# ETH.net
KiCad netlist of a schematic drawn in Altium Designer
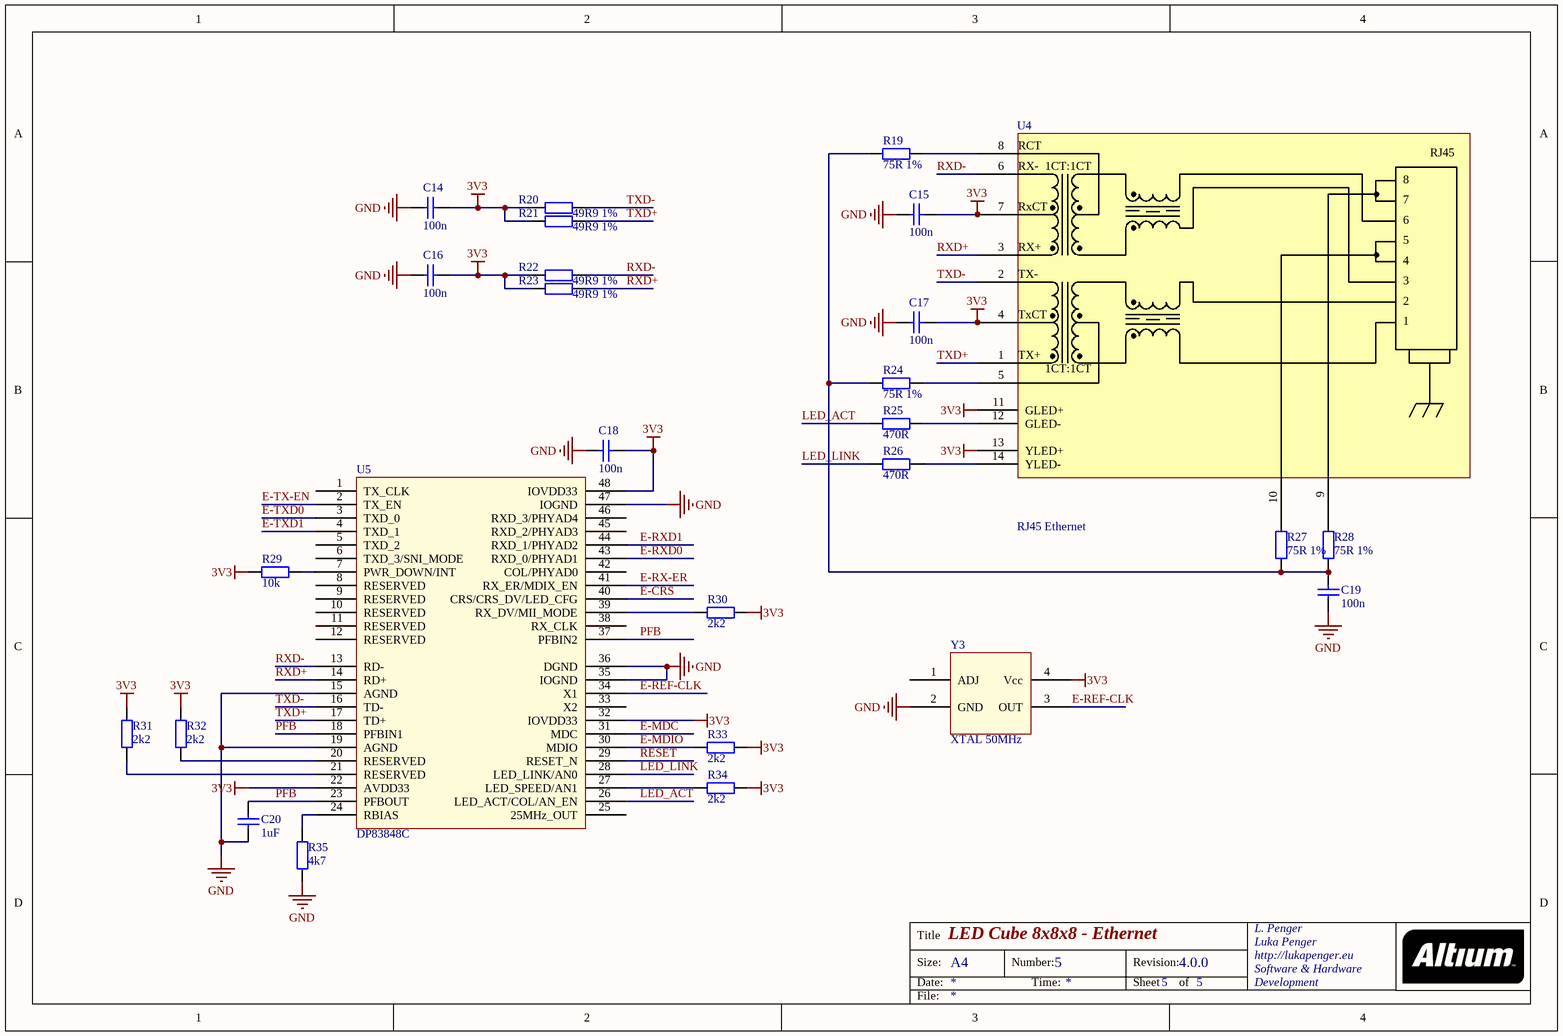
[diagram p0: ETH.SchDoc]

(export (version "E")
  (design (tool "Eeschema 10.0.6"))
  (components
    (comp (ref "C14")
      (value "100n")
      (footprint "1608[0603]")
      (description "Capacitor")
      (fields (field (name "PUBLISHER") "Altium Limited"))
      (libsource (lib "Miscellaneous Devices") (part "Cap"))
    )
    (comp (ref "C15")
      (value "100n")
      (footprint "1608[0603]")
      (description "Capacitor")
      (fields (field (name "PUBLISHER") "Altium Limited"))
      (libsource (lib "Miscellaneous Devices") (part "Cap"))
    )
    (comp (ref "C16")
      (value "100n")
      (footprint "1608[0603]")
      (description "Capacitor")
      (fields (field (name "PUBLISHER") "Altium Limited"))
      (libsource (lib "Miscellaneous Devices") (part "Cap"))
    )
    (comp (ref "C17")
      (value "100n")
      (footprint "1608[0603]")
      (description "Capacitor")
      (fields (field (name "PUBLISHER") "Altium Limited"))
      (libsource (lib "Miscellaneous Devices") (part "Cap"))
    )
    (comp (ref "C18")
      (value "100n")
      (footprint "1608[0603]")
      (description "Capacitor")
      (fields (field (name "PUBLISHER") "Altium Limited"))
      (libsource (lib "Miscellaneous Devices") (part "Cap"))
    )
    (comp (ref "C19")
      (value "100n")
      (footprint "1608[0603]")
      (description "Capacitor")
      (fields (field (name "PUBLISHER") "Altium Limited"))
      (libsource (lib "Miscellaneous Devices") (part "Cap"))
    )
    (comp (ref "C20")
      (value "1uF")
      (footprint "6-0805_L")
      (description "Capacitor")
      (fields (field (name "PUBLISHER") "Altium Limited"))
      (libsource (lib "Miscellaneous Devices") (part "Cap"))
    )
    (comp (ref "R19")
      (value "75R 1%")
      (footprint "1608[0603]")
      (description "Resistor")
      (fields (field (name "PUBLISHER") "Altium Limited"))
      (libsource (lib "Miscellaneous Devices") (part "Res2"))
    )
    (comp (ref "R20")
      (value "49R9 1%")
      (footprint "1608[0603]")
      (description "Resistor")
      (fields (field (name "PUBLISHER") "Altium Limited"))
      (libsource (lib "Miscellaneous Devices") (part "Res2"))
    )
    (comp (ref "R21")
      (value "49R9 1%")
      (footprint "1608[0603]")
      (description "Resistor")
      (fields (field (name "PUBLISHER") "Altium Limited"))
      (libsource (lib "Miscellaneous Devices") (part "Res2"))
    )
    (comp (ref "R22")
      (value "49R9 1%")
      (footprint "1608[0603]")
      (description "Resistor")
      (fields (field (name "PUBLISHER") "Altium Limited"))
      (libsource (lib "Miscellaneous Devices") (part "Res2"))
    )
    (comp (ref "R23")
      (value "49R9 1%")
      (footprint "1608[0603]")
      (description "Resistor")
      (fields (field (name "PUBLISHER") "Altium Limited"))
      (libsource (lib "Miscellaneous Devices") (part "Res2"))
    )
    (comp (ref "R24")
      (value "75R 1%")
      (footprint "1608[0603]")
      (description "Resistor")
      (fields (field (name "PUBLISHER") "Altium Limited"))
      (libsource (lib "Miscellaneous Devices") (part "Res2"))
    )
    (comp (ref "R25")
      (value "470R")
      (footprint "1608[0603]")
      (description "Resistor")
      (fields (field (name "PUBLISHER") "Altium Limited"))
      (libsource (lib "Miscellaneous Devices") (part "Res2"))
    )
    (comp (ref "R26")
      (value "470R")
      (footprint "1608[0603]")
      (description "Resistor")
      (fields (field (name "PUBLISHER") "Altium Limited"))
      (libsource (lib "Miscellaneous Devices") (part "Res2"))
    )
    (comp (ref "R27")
      (value "75R 1%")
      (footprint "1608[0603]")
      (description "Resistor")
      (fields (field (name "PUBLISHER") "Altium Limited"))
      (libsource (lib "") (part "Res2_2"))
    )
    (comp (ref "R28")
      (value "75R 1%")
      (footprint "1608[0603]")
      (description "Resistor")
      (fields (field (name "PUBLISHER") "Altium Limited"))
      (libsource (lib "") (part "Res2_2"))
    )
    (comp (ref "R29")
      (value "10k")
      (footprint "1608[0603]")
      (description "Resistor")
      (fields (field (name "PUBLISHER") "Altium Limited"))
      (libsource (lib "Miscellaneous Devices") (part "Res2"))
    )
    (comp (ref "R30")
      (value "2k2")
      (footprint "1608[0603]")
      (description "Resistor")
      (fields (field (name "PUBLISHER") "Altium Limited"))
      (libsource (lib "Miscellaneous Devices") (part "Res2"))
    )
    (comp (ref "R31")
      (value "2k2")
      (footprint "1608[0603]")
      (description "Resistor")
      (fields (field (name "PUBLISHER") "Altium Limited"))
      (libsource (lib "") (part "Res2_1"))
    )
    (comp (ref "R32")
      (value "2k2")
      (footprint "1608[0603]")
      (description "Resistor")
      (fields (field (name "PUBLISHER") "Altium Limited"))
      (libsource (lib "") (part "Res2_2"))
    )
    (comp (ref "R33")
      (value "2k2")
      (footprint "1608[0603]")
      (description "Resistor")
      (fields (field (name "PUBLISHER") "Altium Limited"))
      (libsource (lib "Miscellaneous Devices") (part "Res2"))
    )
    (comp (ref "R34")
      (value "2k2")
      (footprint "1608[0603]")
      (description "Resistor")
      (fields (field (name "PUBLISHER") "Altium Limited"))
      (libsource (lib "Miscellaneous Devices") (part "Res2"))
    )
    (comp (ref "R35")
      (value "4k7")
      (footprint "1608[0603]")
      (description "Resistor")
      (fields (field (name "PUBLISHER") "Altium Limited"))
      (libsource (lib "") (part "Res2_1"))
    )
    (comp (ref "U4")
      (value "RJ45 Ethernet")
      (footprint "RJ45 Ethernet connector")
      (description "Ethernet Connector")
      (libsource (lib "LP_Lib") (part "RJ45 Ethernet"))
    )
    (comp (ref "U5")
      (value "DP83848C")
      (footprint "DP83848C")
      (description "Ethernet PHY")
      (libsource (lib "LP_Lib") (part "DP83848C"))
    )
    (comp (ref "Y3")
      (value "XTAL 50MHz")
      (footprint "XTAL ACT9200")
      (libsource (lib "LP_Lib") (part "XTAL ACT9200"))
    )
  )
  (nets
    (net (code "1") (name "/E-CRS") (class "Default")
      (node (ref "U5") (pin "40") (pinfunction "CRS/CRS_DV/LED_CFG_40") (pintype "passive"))
    )
    (net (code "2") (name "/E-MDC") (class "Default")
      (node (ref "U5") (pin "31") (pinfunction "MDC_31") (pintype "passive"))
    )
    (net (code "3") (name "/E-MDIO") (class "Default")
      (node (ref "R33") (pin "2") (pinfunction "2_2") (pintype "passive"))
      (node (ref "U5") (pin "30") (pinfunction "MDIO_30") (pintype "passive"))
    )
    (net (code "4") (name "/E-REF-CLK") (class "Default")
      (node (ref "U5") (pin "34") (pinfunction "X1_34") (pintype "passive"))
      (node (ref "Y3") (pin "3") (pinfunction "OUT_3") (pintype "passive"))
    )
    (net (code "5") (name "/E-RX-ER") (class "Default")
      (node (ref "U5") (pin "41") (pinfunction "RX_ER/MDIX_EN_41") (pintype "passive"))
    )
    (net (code "6") (name "/E-RXD0") (class "Default")
      (node (ref "U5") (pin "43") (pinfunction "RXD_0/PHYAD1_43") (pintype "passive"))
    )
    (net (code "7") (name "/E-RXD1") (class "Default")
      (node (ref "U5") (pin "44") (pinfunction "RXD_1/PHYAD2_44") (pintype "passive"))
    )
    (net (code "8") (name "/E-TX-EN") (class "Default")
      (node (ref "U5") (pin "2") (pinfunction "TX_EN_2") (pintype "passive"))
    )
    (net (code "9") (name "/E-TXD0") (class "Default")
      (node (ref "U5") (pin "3") (pinfunction "TXD_0_3") (pintype "passive"))
    )
    (net (code "10") (name "/E-TXD1") (class "Default")
      (node (ref "U5") (pin "4") (pinfunction "TXD_1_4") (pintype "passive"))
    )
    (net (code "11") (name "/LED_ACT") (class "Default")
      (node (ref "R25") (pin "2") (pinfunction "2_2") (pintype "passive"))
      (node (ref "U5") (pin "26") (pinfunction "LED_ACT/COL/AN_EN_26") (pintype "passive"))
    )
    (net (code "12") (name "/LED_LINK") (class "Default")
      (node (ref "R26") (pin "2") (pinfunction "2_2") (pintype "passive"))
      (node (ref "U5") (pin "28") (pinfunction "LED_LINK/AN0_28") (pintype "passive"))
    )
    (net (code "13") (name "/PFB") (class "Default")
      (node (ref "C20") (pin "1") (pinfunction "1_1") (pintype "passive"))
      (node (ref "U5") (pin "18") (pinfunction "PFBIN1_18") (pintype "passive"))
      (node (ref "U5") (pin "23") (pinfunction "PFBOUT_23") (pintype "passive"))
      (node (ref "U5") (pin "37") (pinfunction "PFBIN2_37") (pintype "passive"))
    )
    (net (code "14") (name "/RESET") (class "Default")
      (node (ref "U5") (pin "29") (pinfunction "RESET_N_29") (pintype "passive"))
    )
    (net (code "15") (name "/RXD+") (class "Default")
      (node (ref "R23") (pin "1") (pinfunction "1_1") (pintype "passive"))
      (node (ref "U4") (pin "3") (pintype "passive"))
      (node (ref "U5") (pin "14") (pinfunction "RD+_14") (pintype "passive"))
    )
    (net (code "16") (name "/RXD-") (class "Default")
      (node (ref "R22") (pin "1") (pinfunction "1_1") (pintype "passive"))
      (node (ref "U4") (pin "6") (pintype "passive"))
      (node (ref "U5") (pin "13") (pinfunction "RD-_13") (pintype "passive"))
    )
    (net (code "17") (name "/TXD+") (class "Default")
      (node (ref "R21") (pin "1") (pinfunction "1_1") (pintype "passive"))
      (node (ref "U4") (pin "1") (pintype "passive"))
      (node (ref "U5") (pin "17") (pinfunction "TD+_17") (pintype "passive"))
    )
    (net (code "18") (name "/TXD-") (class "Default")
      (node (ref "R20") (pin "1") (pinfunction "1_1") (pintype "passive"))
      (node (ref "U4") (pin "2") (pintype "passive"))
      (node (ref "U5") (pin "16") (pinfunction "TD-_16") (pintype "passive"))
    )
    (net (code "19") (name "3V3") (class "Default")
      (node (ref "C14") (pin "2") (pinfunction "2_2") (pintype "passive"))
      (node (ref "C15") (pin "2") (pinfunction "2_2") (pintype "passive"))
      (node (ref "C16") (pin "2") (pinfunction "2_2") (pintype "passive"))
      (node (ref "C17") (pin "2") (pinfunction "2_2") (pintype "passive"))
      (node (ref "C18") (pin "2") (pinfunction "2_2") (pintype "passive"))
      (node (ref "R20") (pin "2") (pinfunction "2_2") (pintype "passive"))
      (node (ref "R21") (pin "2") (pinfunction "2_2") (pintype "passive"))
      (node (ref "R22") (pin "2") (pinfunction "2_2") (pintype "passive"))
      (node (ref "R23") (pin "2") (pinfunction "2_2") (pintype "passive"))
      (node (ref "R29") (pin "2") (pinfunction "2_2") (pintype "passive"))
      (node (ref "R30") (pin "1") (pinfunction "1_1") (pintype "passive"))
      (node (ref "R31") (pin "1") (pinfunction "1_1") (pintype "passive"))
      (node (ref "R32") (pin "2") (pinfunction "2_2") (pintype "passive"))
      (node (ref "R33") (pin "1") (pinfunction "1_1") (pintype "passive"))
      (node (ref "R34") (pin "1") (pinfunction "1_1") (pintype "passive"))
      (node (ref "U4") (pin "11") (pinfunction "GLED+_11") (pintype "passive"))
      (node (ref "U4") (pin "13") (pinfunction "YLED+_13") (pintype "passive"))
      (node (ref "U4") (pin "4") (pintype "passive"))
      (node (ref "U4") (pin "7") (pintype "passive"))
      (node (ref "U5") (pin "22") (pinfunction "AVDD33_22") (pintype "passive"))
      (node (ref "U5") (pin "32") (pinfunction "IOVDD33_32") (pintype "passive"))
      (node (ref "U5") (pin "48") (pinfunction "IOVDD33_48") (pintype "passive"))
      (node (ref "Y3") (pin "4") (pinfunction "Vcc_4") (pintype "passive"))
    )
    (net (code "20") (name "GND") (class "Default")
      (node (ref "C14") (pin "1") (pinfunction "1_1") (pintype "passive"))
      (node (ref "C15") (pin "1") (pinfunction "1_1") (pintype "passive"))
      (node (ref "C16") (pin "1") (pinfunction "1_1") (pintype "passive"))
      (node (ref "C17") (pin "1") (pinfunction "1_1") (pintype "passive"))
      (node (ref "C18") (pin "1") (pinfunction "1_1") (pintype "passive"))
      (node (ref "C19") (pin "2") (pinfunction "2_2") (pintype "passive"))
      (node (ref "C20") (pin "2") (pinfunction "2_2") (pintype "passive"))
      (node (ref "R35") (pin "2") (pinfunction "2_2") (pintype "passive"))
      (node (ref "U5") (pin "15") (pinfunction "AGND_15") (pintype "passive"))
      (node (ref "U5") (pin "19") (pinfunction "AGND_19") (pintype "passive"))
      (node (ref "U5") (pin "35") (pinfunction "IOGND_35") (pintype "passive"))
      (node (ref "U5") (pin "36") (pinfunction "DGND_36") (pintype "passive"))
      (node (ref "U5") (pin "47") (pinfunction "IOGND_47") (pintype "passive"))
      (node (ref "Y3") (pin "2") (pinfunction "GND_2") (pintype "passive"))
    )
    (net (code "21") (name "Net-(C19-Pad1)") (class "Default")
      (node (ref "C19") (pin "1") (pinfunction "1_1") (pintype "passive"))
      (node (ref "R19") (pin "2") (pinfunction "2_2") (pintype "passive"))
      (node (ref "R24") (pin "2") (pinfunction "2_2") (pintype "passive"))
      (node (ref "R27") (pin "1") (pinfunction "1_1") (pintype "passive"))
      (node (ref "R28") (pin "1") (pinfunction "1_1") (pintype "passive"))
    )
    (net (code "22") (name "Net-(R19-Pad1)") (class "Default")
      (node (ref "R19") (pin "1") (pinfunction "1_1") (pintype "passive"))
      (node (ref "U4") (pin "8") (pintype "passive"))
    )
    (net (code "23") (name "Net-(R24-Pad1)") (class "Default")
      (node (ref "R24") (pin "1") (pinfunction "1_1") (pintype "passive"))
      (node (ref "U4") (pin "5") (pintype "passive"))
    )
    (net (code "24") (name "Net-(R27-Pad2)") (class "Default")
      (node (ref "R27") (pin "2") (pinfunction "2_2") (pintype "passive"))
      (node (ref "U4") (pin "10") (pintype "passive"))
    )
    (net (code "25") (name "Net-(R28-Pad2)") (class "Default")
      (node (ref "R28") (pin "2") (pinfunction "2_2") (pintype "passive"))
      (node (ref "U4") (pin "9") (pintype "passive"))
    )
    (net (code "26") (name "Net-(R31-Pad2)") (class "Default")
      (node (ref "R31") (pin "2") (pinfunction "2_2") (pintype "passive"))
      (node (ref "U5") (pin "21") (pinfunction "RESERVED_21") (pintype "passive"))
    )
    (net (code "27") (name "Net-(R32-Pad1)") (class "Default")
      (node (ref "R32") (pin "1") (pinfunction "1_1") (pintype "passive"))
      (node (ref "U5") (pin "20") (pinfunction "RESERVED_20") (pintype "passive"))
    )
    (net (code "28") (name "Net-(U4-GLED-)") (class "Default")
      (node (ref "R25") (pin "1") (pinfunction "1_1") (pintype "passive"))
      (node (ref "U4") (pin "12") (pinfunction "GLED-_12") (pintype "passive"))
    )
    (net (code "29") (name "Net-(U4-YLED-)") (class "Default")
      (node (ref "R26") (pin "1") (pinfunction "1_1") (pintype "passive"))
      (node (ref "U4") (pin "14") (pinfunction "YLED-_14") (pintype "passive"))
    )
    (net (code "30") (name "Net-(U5-LED_SPEED{slash}AN1)") (class "Default")
      (node (ref "R34") (pin "2") (pinfunction "2_2") (pintype "passive"))
      (node (ref "U5") (pin "27") (pinfunction "LED_SPEED/AN1_27") (pintype "passive"))
    )
    (net (code "31") (name "Net-(U5-PWR_DOWN{slash}INT)") (class "Default")
      (node (ref "R29") (pin "1") (pinfunction "1_1") (pintype "passive"))
      (node (ref "U5") (pin "7") (pinfunction "PWR_DOWN/INT_7") (pintype "passive"))
    )
    (net (code "32") (name "Net-(U5-RBIAS)") (class "Default")
      (node (ref "R35") (pin "1") (pinfunction "1_1") (pintype "passive"))
      (node (ref "U5") (pin "24") (pinfunction "RBIAS_24") (pintype "passive"))
    )
    (net (code "33") (name "Net-(U5-RX_DV{slash}MII_MODE)") (class "Default")
      (node (ref "R30") (pin "2") (pinfunction "2_2") (pintype "passive"))
      (node (ref "U5") (pin "39") (pinfunction "RX_DV/MII_MODE_39") (pintype "passive"))
    )
    (net (code "34") (name "unconnected-(U5-25MHz_OUT-Pad25)") (class "Default")
      (node (ref "U5") (pin "25") (pinfunction "25MHz_OUT_25") (pintype "passive"))
    )
    (net (code "35") (name "unconnected-(U5-COL{slash}PHYAD0-Pad42)") (class "Default")
      (node (ref "U5") (pin "42") (pinfunction "COL/PHYAD0_42") (pintype "passive"))
    )
    (net (code "36") (name "unconnected-(U5-RESERVED-Pad8)") (class "Default")
      (node (ref "U5") (pin "8") (pinfunction "RESERVED_8") (pintype "passive"))
    )
    (net (code "37") (name "unconnected-(U5-RESERVED-Pad9)") (class "Default")
      (node (ref "U5") (pin "9") (pinfunction "RESERVED_9") (pintype "passive"))
    )
    (net (code "38") (name "unconnected-(U5-RESERVED-Pad10)") (class "Default")
      (node (ref "U5") (pin "10") (pinfunction "RESERVED_10") (pintype "passive"))
    )
    (net (code "39") (name "unconnected-(U5-RESERVED-Pad11)") (class "Default")
      (node (ref "U5") (pin "11") (pinfunction "RESERVED_11") (pintype "passive"))
    )
    (net (code "40") (name "unconnected-(U5-RESERVED-Pad12)") (class "Default")
      (node (ref "U5") (pin "12") (pinfunction "RESERVED_12") (pintype "passive"))
    )
    (net (code "41") (name "unconnected-(U5-RXD_2{slash}PHYAD3-Pad45)") (class "Default")
      (node (ref "U5") (pin "45") (pinfunction "RXD_2/PHYAD3_45") (pintype "passive"))
    )
    (net (code "42") (name "unconnected-(U5-RXD_3{slash}PHYAD4-Pad46)") (class "Default")
      (node (ref "U5") (pin "46") (pinfunction "RXD_3/PHYAD4_46") (pintype "passive"))
    )
    (net (code "43") (name "unconnected-(U5-RX_CLK-Pad38)") (class "Default")
      (node (ref "U5") (pin "38") (pinfunction "RX_CLK_38") (pintype "passive"))
    )
    (net (code "44") (name "unconnected-(U5-TXD_2-Pad5)") (class "Default")
      (node (ref "U5") (pin "5") (pinfunction "TXD_2_5") (pintype "passive"))
    )
    (net (code "45") (name "unconnected-(U5-TXD_3{slash}SNI_MODE-Pad6)") (class "Default")
      (node (ref "U5") (pin "6") (pinfunction "TXD_3/SNI_MODE_6") (pintype "passive"))
    )
    (net (code "46") (name "unconnected-(U5-TX_CLK-Pad1)") (class "Default")
      (node (ref "U5") (pin "1") (pinfunction "TX_CLK_1") (pintype "passive"))
    )
    (net (code "47") (name "unconnected-(U5-X2-Pad33)") (class "Default")
      (node (ref "U5") (pin "33") (pinfunction "X2_33") (pintype "passive"))
    )
    (net (code "48") (name "unconnected-(Y3-ADJ-Pad1)") (class "Default")
      (node (ref "Y3") (pin "1") (pinfunction "ADJ_1") (pintype "passive"))
    )
  )
)
